# Power.net
KiCad netlist of a schematic drawn in Altium Designer
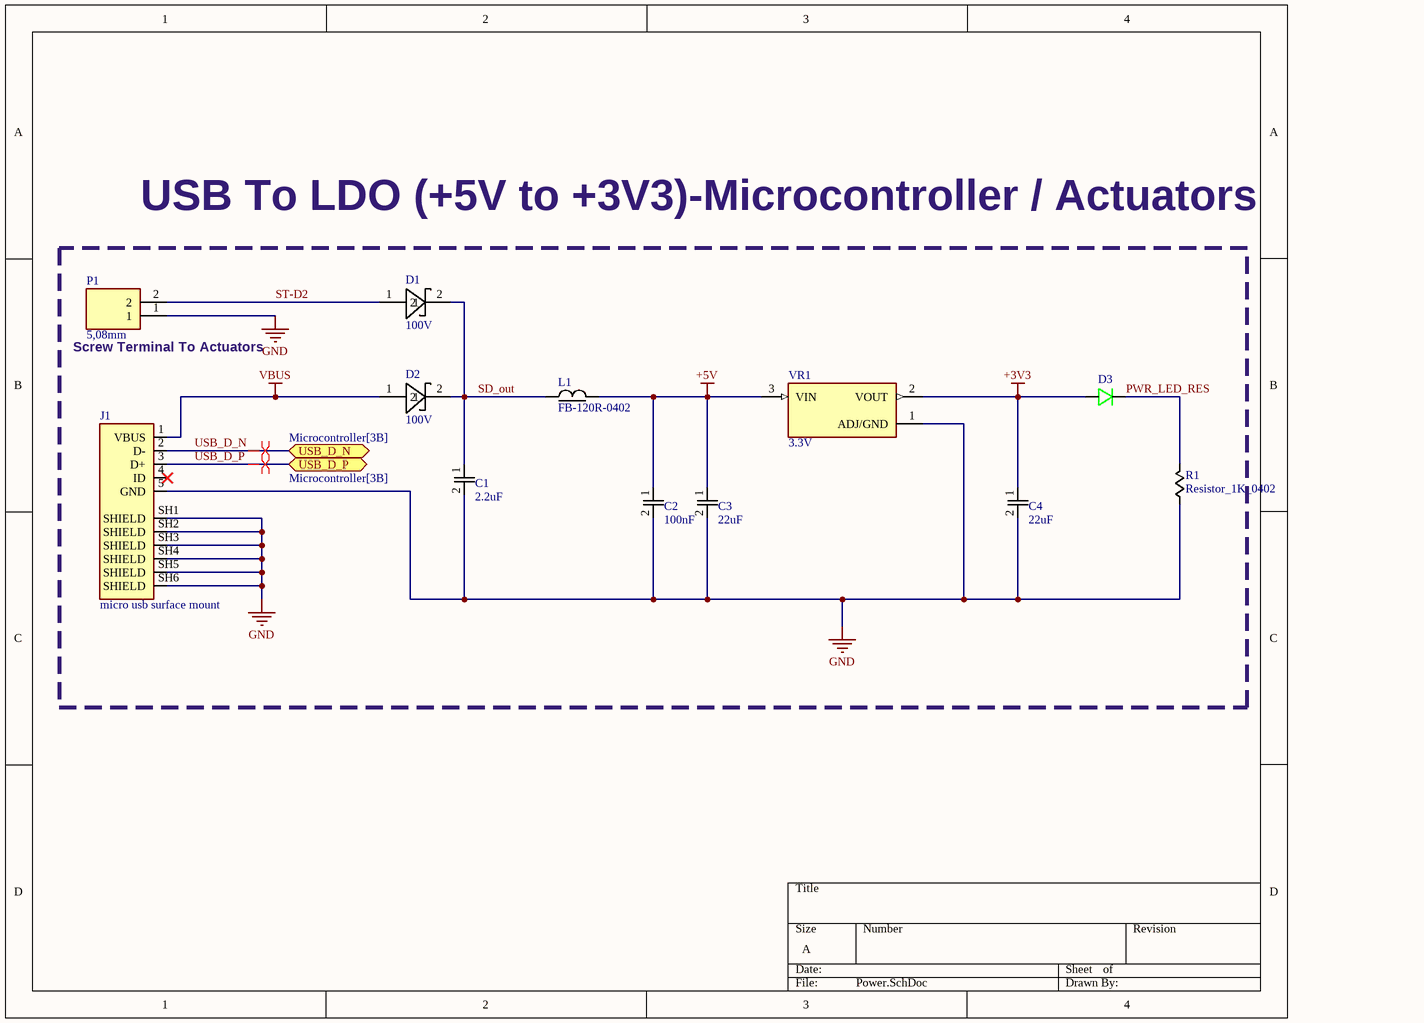
[diagram p0: Power.SchDoc]

(export (version "E")
  (design (tool "Eeschema 10.0.6"))
  (components
    (comp (ref "C1")
      (value "2.2uF")
      (footprint "CAPC1005X55N")
      (description "CAP CER 2.2uF 16V X5R 0402")
      (fields
        (field (name "MANUFACTURER") "Samsung Electro-Mechanics")
        (field (name "MANUFACTURER PART #") "CL05A225KO5NQNC")
      )
      (libsource (lib "Power") (part "Cap_2.2uF_0402"))
    )
    (comp (ref "C2")
      (value "100nF")
      (footprint "CAPC1005X55N")
      (description "CAP CER 100nF 16V X7R 0402")
      (fields
        (field (name "MANUFACTURER") "Samsung Electro-Mechanics")
        (field (name "MANUFACTURER PART #") "CL05B104KO5NNNC")
      )
      (libsource (lib "All Components") (part "Cap_100nF_0402"))
    )
    (comp (ref "C3")
      (value "22uF")
      (footprint "CAPC1005X55N")
      (description "CAP CER 22uF 6.3V X5R 0402")
      (fields
        (field (name "MANUFACTURER") "Samsung Electro-Mechanics")
        (field (name "MANUFACTURER PART #") "CL05A226MQ5QUNC")
      )
      (libsource (lib "Power") (part "Cap_22uF_0402"))
    )
    (comp (ref "C4")
      (value "22uF")
      (footprint "CAPC1005X55N")
      (description "CAP CER 22uF 6.3V X5R 0402")
      (fields
        (field (name "MANUFACTURER") "Samsung Electro-Mechanics")
        (field (name "MANUFACTURER PART #") "CL05A226MQ5QUNC")
      )
      (libsource (lib "Power") (part "Cap_22uF_0402"))
    )
    (comp (ref "D1")
      (value "100V")
      (footprint "Schottky.D")
      (description "100V 850mV@5A 5A SMAG Schottky Diodes ROHS")
      (fields (field (name "MANUFACTURER") "Nexperia") (field (name "MFR. PART #") "BAT54S,215"))
      (libsource (lib "Power") (part "Schottky_D"))
    )
    (comp (ref "D2")
      (value "100V")
      (footprint "Schottky.D")
      (description "100V 850mV@5A 5A SMAG Schottky Diodes ROHS")
      (fields (field (name "MANUFACTURER") "Nexperia") (field (name "MFR. PART #") "BAT54S,215"))
      (libsource (lib "Power") (part "Schottky_D"))
    )
    (comp (ref "D3")
      (value "Green LED 0805")
      (footprint "LED_APT2012MGC")
      (description "LED GREEN 0805 SMD")
      (fields (field (name "MANUFACTURER") "NATIONSTAR") (field (name "MANUFACTURER PART#") "NCD0805G1"))
      (libsource (lib "Power") (part "Green LED 0805"))
    )
    (comp (ref "J1")
      (value "micro usb surface mount")
      (footprint "TE_1981568-1")
      (description "MICRO USB, TYPE B,")
      (fields (field (name "MANUFACTURER") "HMTCONN") (field (name "MANUFACTURER PART#") "HMT-MICRO USB 4P"))
      (libsource (lib "Power") (part "micro usb surface mount"))
    )
    (comp (ref "L1")
      (value "FB-120R-0402")
      (footprint "RESC1005X40N")
      (description "FERRITE BEAD 120Ω 0402")
      (fields
        (field (name "MANUFACTURER") "KOHERelec")
        (field (name "MANUFACTURER PART#") "FBHA0402-121-202R")
      )
      (libsource (lib "Power") (part "FB-120R-0402"))
    )
    (comp (ref "P1")
      (value "5,08mm")
      (footprint "Screw_terminal_block_5.0")
      (fields
        (field (name "MANUFACTURER") "KANGNEX")
        (field (name "MFR. PART #") "WJ500V-5.08-2P")
        (field (name "SPLR.PART#") "C8465")
      )
      (libsource (lib "Power") (part "screw terminal block 2 port"))
    )
    (comp (ref "R1")
      (value "Resistor_1K_0402")
      (footprint "RESC1005X40N")
      (description "1kOhms Â±1% 0.063W, 1/16W Chip Resistor 0402 (1005 Metric) Moisture Resistant Thick Film")
      (fields (field (name "MANUFACTURER") "FOJAN") (field (name "MANUFACTURER PART #") "RC0402FR-071KL"))
      (libsource (lib "Power") (part "Resistor_1K_0402"))
    )
    (comp (ref "VR1")
      (value "3.3V")
      (footprint "SOT229P700X180-4N")
      (fields
        (field (name "MANUFACTURER") "Advanced Monolithic Systems")
        (field (name "MFR. PART #") "AMS1117-3.3")
        (field (name "SPLR.PART#") "C6186")
      )
      (libsource (lib "Power") (part "AMS1117_3.3"))
    )
  )
  (nets
    (net (code "1") (name "+3V3") (class "Default")
      (node (ref "C4") (pin "1") (pinfunction "1_1") (pintype "passive"))
      (node (ref "D3") (pin "A") (pinfunction "A_A") (pintype "passive"))
      (node (ref "VR1") (pin "2") (pinfunction "VOUT_2") (pintype "output"))
    )
    (net (code "2") (name "+5V") (class "Default")
      (node (ref "C2") (pin "1") (pinfunction "1_1") (pintype "passive"))
      (node (ref "C3") (pin "1") (pinfunction "1_1") (pintype "passive"))
      (node (ref "L1") (pin "2") (pinfunction "2_2") (pintype "passive"))
      (node (ref "VR1") (pin "3") (pinfunction "VIN_3") (pintype "input"))
    )
    (net (code "3") (name "/PWR_LED_RES") (class "Default")
      (node (ref "D3") (pin "C") (pinfunction "C_C") (pintype "passive"))
      (node (ref "R1") (pin "2") (pinfunction "2_2") (pintype "passive"))
    )
    (net (code "4") (name "/SD_out") (class "Default")
      (node (ref "C1") (pin "1") (pinfunction "1_1") (pintype "passive"))
      (node (ref "D1") (pin "2") (pinfunction "2_2") (pintype "passive"))
      (node (ref "D2") (pin "2") (pinfunction "2_2") (pintype "passive"))
      (node (ref "L1") (pin "1") (pinfunction "1_1") (pintype "passive"))
    )
    (net (code "5") (name "/ST-D2") (class "Default")
      (node (ref "D1") (pin "1") (pinfunction "1_1") (pintype "passive"))
      (node (ref "P1") (pin "2") (pinfunction "2_2") (pintype "passive"))
    )
    (net (code "6") (name "/USB_D_N") (class "Default")
      (node (ref "J1") (pin "2") (pinfunction "D-_2") (pintype "passive"))
    )
    (net (code "7") (name "/USB_D_P") (class "Default")
      (node (ref "J1") (pin "3") (pinfunction "D+_3") (pintype "passive"))
    )
    (net (code "8") (name "GND") (class "Default")
      (node (ref "C1") (pin "2") (pinfunction "2_2") (pintype "passive"))
      (node (ref "C2") (pin "2") (pinfunction "2_2") (pintype "passive"))
      (node (ref "C3") (pin "2") (pinfunction "2_2") (pintype "passive"))
      (node (ref "C4") (pin "2") (pinfunction "2_2") (pintype "passive"))
      (node (ref "J1") (pin "5") (pinfunction "GND_5") (pintype "passive"))
      (node (ref "J1") (pin "SH1") (pinfunction "SHIELD_SH1") (pintype "passive"))
      (node (ref "J1") (pin "SH2") (pinfunction "SHIELD_SH2") (pintype "passive"))
      (node (ref "J1") (pin "SH3") (pinfunction "SHIELD_SH3") (pintype "passive"))
      (node (ref "J1") (pin "SH4") (pinfunction "SHIELD_SH4") (pintype "passive"))
      (node (ref "J1") (pin "SH5") (pinfunction "SHIELD_SH5") (pintype "passive"))
      (node (ref "J1") (pin "SH6") (pinfunction "SHIELD_SH6") (pintype "passive"))
      (node (ref "P1") (pin "1") (pinfunction "1_1") (pintype "passive"))
      (node (ref "R1") (pin "1") (pinfunction "1_1") (pintype "passive"))
      (node (ref "VR1") (pin "1") (pinfunction "ADJ/GND_1") (pintype "power_in"))
    )
    (net (code "9") (name "VBUS") (class "Default")
      (node (ref "D2") (pin "1") (pinfunction "1_1") (pintype "passive"))
      (node (ref "J1") (pin "1") (pinfunction "VBUS_1") (pintype "passive"))
    )
    (net (code "10") (name "unconnected-(J1-ID-Pad4)") (class "Default")
      (node (ref "J1") (pin "4") (pinfunction "ID_4") (pintype "passive+no_connect"))
    )
  )
)
